# Interconnect_board_limit_switches_v1p1.net
KiCad netlist of a schematic drawn in EAGLE
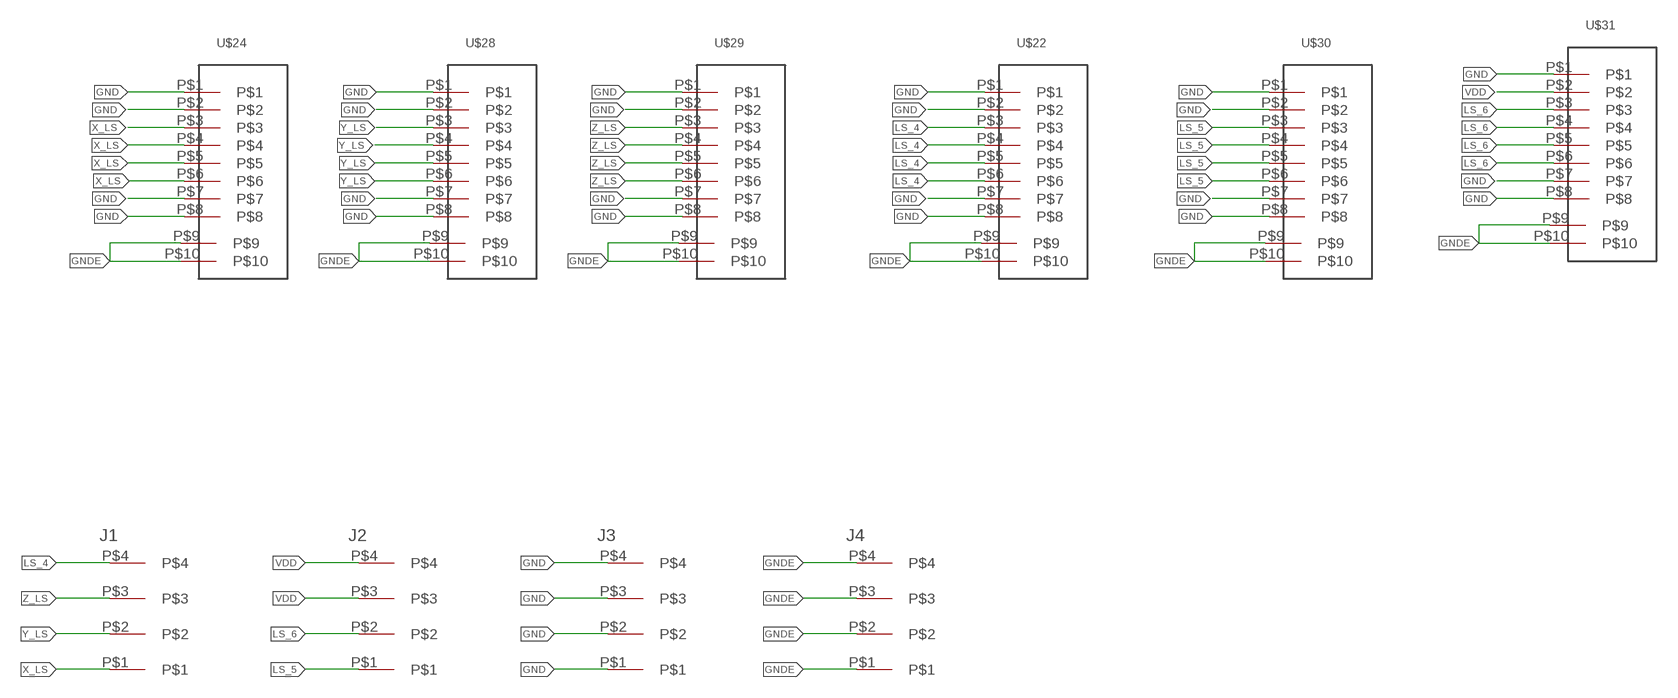
[diagram p0: schematic, sheet 1]

(export (version "E")
  (design (tool "Eeschema 10.0.6"))
  (components
    (comp (ref "J1")
      (value "3.81MM_1_X_4_RT_ANGLE_PLUG_HEADER")
      (footprint "eagle-import:1X4_3.81MM_PITCH")
      (libsource (lib "eagle-import") (part "3.81MM_1_X_4_RT_ANGLE_PLUG_HEADER"))
    )
    (comp (ref "J2")
      (value "3.81MM_1_X_4_RT_ANGLE_PLUG_HEADER")
      (footprint "eagle-import:1X4_3.81MM_PITCH")
      (libsource (lib "eagle-import") (part "3.81MM_1_X_4_RT_ANGLE_PLUG_HEADER"))
    )
    (comp (ref "J3")
      (value "3.81MM_1_X_4_RT_ANGLE_PLUG_HEADER")
      (footprint "eagle-import:1X4_3.81MM_PITCH")
      (libsource (lib "eagle-import") (part "3.81MM_1_X_4_RT_ANGLE_PLUG_HEADER"))
    )
    (comp (ref "J4")
      (value "3.81MM_1_X_4_RT_ANGLE_PLUG_HEADER")
      (footprint "eagle-import:1X4_3.81MM_PITCH")
      (libsource (lib "eagle-import") (part "3.81MM_1_X_4_RT_ANGLE_PLUG_HEADER"))
    )
    (comp (ref "U$22")
      (value "RJ45_SMTRJ")
      (footprint "eagle-import:RJ45_SMT")
      (libsource (lib "eagle-import") (part "RJ45_SMTRJ"))
    )
    (comp (ref "U$24")
      (value "RJ45_SMTRJ")
      (footprint "eagle-import:RJ45_SMT")
      (libsource (lib "eagle-import") (part "RJ45_SMTRJ"))
    )
    (comp (ref "U$28")
      (value "RJ45_SMTRJ")
      (footprint "eagle-import:RJ45_SMT")
      (libsource (lib "eagle-import") (part "RJ45_SMTRJ"))
    )
    (comp (ref "U$29")
      (value "RJ45_SMTRJ")
      (footprint "eagle-import:RJ45_SMT")
      (libsource (lib "eagle-import") (part "RJ45_SMTRJ"))
    )
    (comp (ref "U$30")
      (value "RJ45_SMTRJ")
      (footprint "eagle-import:RJ45_SMT")
      (libsource (lib "eagle-import") (part "RJ45_SMTRJ"))
    )
    (comp (ref "U$31")
      (value "RJ45_SMTRJ")
      (footprint "eagle-import:RJ45_SMT")
      (libsource (lib "eagle-import") (part "RJ45_SMTRJ"))
    )
  )
  (nets
    (net (code "1") (name "GND") (class "Default")
      (node (ref "J3") (pin "P$1") (pinfunction "P$1_P$1") (pintype "bidirectional"))
      (node (ref "J3") (pin "P$2") (pinfunction "P$2_P$2") (pintype "bidirectional"))
      (node (ref "J3") (pin "P$3") (pinfunction "P$3_P$3") (pintype "bidirectional"))
      (node (ref "J3") (pin "P$4") (pinfunction "P$4_P$4") (pintype "bidirectional"))
      (node (ref "U$22") (pin "P$1") (pinfunction "P$1_P$1") (pintype "bidirectional"))
      (node (ref "U$22") (pin "P$2") (pinfunction "P$2_P$2") (pintype "bidirectional"))
      (node (ref "U$22") (pin "P$7") (pinfunction "P$7_P$7") (pintype "bidirectional"))
      (node (ref "U$22") (pin "P$8") (pinfunction "P$8_P$8") (pintype "bidirectional"))
      (node (ref "U$24") (pin "P$1") (pinfunction "P$1_P$1") (pintype "bidirectional"))
      (node (ref "U$24") (pin "P$2") (pinfunction "P$2_P$2") (pintype "bidirectional"))
      (node (ref "U$24") (pin "P$7") (pinfunction "P$7_P$7") (pintype "bidirectional"))
      (node (ref "U$24") (pin "P$8") (pinfunction "P$8_P$8") (pintype "bidirectional"))
      (node (ref "U$28") (pin "P$1") (pinfunction "P$1_P$1") (pintype "bidirectional"))
      (node (ref "U$28") (pin "P$2") (pinfunction "P$2_P$2") (pintype "bidirectional"))
      (node (ref "U$28") (pin "P$7") (pinfunction "P$7_P$7") (pintype "bidirectional"))
      (node (ref "U$28") (pin "P$8") (pinfunction "P$8_P$8") (pintype "bidirectional"))
      (node (ref "U$29") (pin "P$1") (pinfunction "P$1_P$1") (pintype "bidirectional"))
      (node (ref "U$29") (pin "P$2") (pinfunction "P$2_P$2") (pintype "bidirectional"))
      (node (ref "U$29") (pin "P$7") (pinfunction "P$7_P$7") (pintype "bidirectional"))
      (node (ref "U$29") (pin "P$8") (pinfunction "P$8_P$8") (pintype "bidirectional"))
      (node (ref "U$30") (pin "P$1") (pinfunction "P$1_P$1") (pintype "bidirectional"))
      (node (ref "U$30") (pin "P$2") (pinfunction "P$2_P$2") (pintype "bidirectional"))
      (node (ref "U$30") (pin "P$7") (pinfunction "P$7_P$7") (pintype "bidirectional"))
      (node (ref "U$30") (pin "P$8") (pinfunction "P$8_P$8") (pintype "bidirectional"))
      (node (ref "U$31") (pin "P$1") (pinfunction "P$1_P$1") (pintype "bidirectional"))
      (node (ref "U$31") (pin "P$7") (pinfunction "P$7_P$7") (pintype "bidirectional"))
      (node (ref "U$31") (pin "P$8") (pinfunction "P$8_P$8") (pintype "bidirectional"))
    )
    (net (code "2") (name "GNDE") (class "Default")
      (node (ref "J4") (pin "P$1") (pinfunction "P$1_P$1") (pintype "bidirectional"))
      (node (ref "J4") (pin "P$2") (pinfunction "P$2_P$2") (pintype "bidirectional"))
      (node (ref "J4") (pin "P$3") (pinfunction "P$3_P$3") (pintype "bidirectional"))
      (node (ref "J4") (pin "P$4") (pinfunction "P$4_P$4") (pintype "bidirectional"))
      (node (ref "U$22") (pin "P$10") (pinfunction "P$10_P$10") (pintype "bidirectional"))
      (node (ref "U$22") (pin "P$9") (pinfunction "P$9_P$9") (pintype "bidirectional"))
      (node (ref "U$24") (pin "P$10") (pinfunction "P$10_P$10") (pintype "bidirectional"))
      (node (ref "U$24") (pin "P$9") (pinfunction "P$9_P$9") (pintype "bidirectional"))
      (node (ref "U$28") (pin "P$10") (pinfunction "P$10_P$10") (pintype "bidirectional"))
      (node (ref "U$28") (pin "P$9") (pinfunction "P$9_P$9") (pintype "bidirectional"))
      (node (ref "U$29") (pin "P$10") (pinfunction "P$10_P$10") (pintype "bidirectional"))
      (node (ref "U$29") (pin "P$9") (pinfunction "P$9_P$9") (pintype "bidirectional"))
      (node (ref "U$30") (pin "P$10") (pinfunction "P$10_P$10") (pintype "bidirectional"))
      (node (ref "U$30") (pin "P$9") (pinfunction "P$9_P$9") (pintype "bidirectional"))
      (node (ref "U$31") (pin "P$10") (pinfunction "P$10_P$10") (pintype "bidirectional"))
      (node (ref "U$31") (pin "P$9") (pinfunction "P$9_P$9") (pintype "bidirectional"))
    )
    (net (code "3") (name "LS_4") (class "Default")
      (node (ref "J1") (pin "P$4") (pinfunction "P$4_P$4") (pintype "bidirectional"))
      (node (ref "U$22") (pin "P$3") (pinfunction "P$3_P$3") (pintype "bidirectional"))
      (node (ref "U$22") (pin "P$4") (pinfunction "P$4_P$4") (pintype "bidirectional"))
      (node (ref "U$22") (pin "P$5") (pinfunction "P$5_P$5") (pintype "bidirectional"))
      (node (ref "U$22") (pin "P$6") (pinfunction "P$6_P$6") (pintype "bidirectional"))
    )
    (net (code "4") (name "LS_5") (class "Default")
      (node (ref "J2") (pin "P$1") (pinfunction "P$1_P$1") (pintype "bidirectional"))
      (node (ref "U$30") (pin "P$3") (pinfunction "P$3_P$3") (pintype "bidirectional"))
      (node (ref "U$30") (pin "P$4") (pinfunction "P$4_P$4") (pintype "bidirectional"))
      (node (ref "U$30") (pin "P$5") (pinfunction "P$5_P$5") (pintype "bidirectional"))
      (node (ref "U$30") (pin "P$6") (pinfunction "P$6_P$6") (pintype "bidirectional"))
    )
    (net (code "5") (name "LS_6") (class "Default")
      (node (ref "J2") (pin "P$2") (pinfunction "P$2_P$2") (pintype "bidirectional"))
      (node (ref "U$31") (pin "P$3") (pinfunction "P$3_P$3") (pintype "bidirectional"))
      (node (ref "U$31") (pin "P$4") (pinfunction "P$4_P$4") (pintype "bidirectional"))
      (node (ref "U$31") (pin "P$5") (pinfunction "P$5_P$5") (pintype "bidirectional"))
      (node (ref "U$31") (pin "P$6") (pinfunction "P$6_P$6") (pintype "bidirectional"))
    )
    (net (code "6") (name "VDD") (class "Default")
      (node (ref "J2") (pin "P$3") (pinfunction "P$3_P$3") (pintype "bidirectional"))
      (node (ref "J2") (pin "P$4") (pinfunction "P$4_P$4") (pintype "bidirectional"))
      (node (ref "U$31") (pin "P$2") (pinfunction "P$2_P$2") (pintype "bidirectional"))
    )
    (net (code "7") (name "X_LS") (class "Default")
      (node (ref "J1") (pin "P$1") (pinfunction "P$1_P$1") (pintype "bidirectional"))
      (node (ref "U$24") (pin "P$3") (pinfunction "P$3_P$3") (pintype "bidirectional"))
      (node (ref "U$24") (pin "P$4") (pinfunction "P$4_P$4") (pintype "bidirectional"))
      (node (ref "U$24") (pin "P$5") (pinfunction "P$5_P$5") (pintype "bidirectional"))
      (node (ref "U$24") (pin "P$6") (pinfunction "P$6_P$6") (pintype "bidirectional"))
    )
    (net (code "8") (name "Y_LS") (class "Default")
      (node (ref "J1") (pin "P$2") (pinfunction "P$2_P$2") (pintype "bidirectional"))
      (node (ref "U$28") (pin "P$3") (pinfunction "P$3_P$3") (pintype "bidirectional"))
      (node (ref "U$28") (pin "P$4") (pinfunction "P$4_P$4") (pintype "bidirectional"))
      (node (ref "U$28") (pin "P$5") (pinfunction "P$5_P$5") (pintype "bidirectional"))
      (node (ref "U$28") (pin "P$6") (pinfunction "P$6_P$6") (pintype "bidirectional"))
    )
    (net (code "9") (name "Z_LS") (class "Default")
      (node (ref "J1") (pin "P$3") (pinfunction "P$3_P$3") (pintype "bidirectional"))
      (node (ref "U$29") (pin "P$3") (pinfunction "P$3_P$3") (pintype "bidirectional"))
      (node (ref "U$29") (pin "P$4") (pinfunction "P$4_P$4") (pintype "bidirectional"))
      (node (ref "U$29") (pin "P$5") (pinfunction "P$5_P$5") (pintype "bidirectional"))
      (node (ref "U$29") (pin "P$6") (pinfunction "P$6_P$6") (pintype "bidirectional"))
    )
  )
)
